# hv_pm.net
KiCad netlist of a schematic drawn in Altium Designer
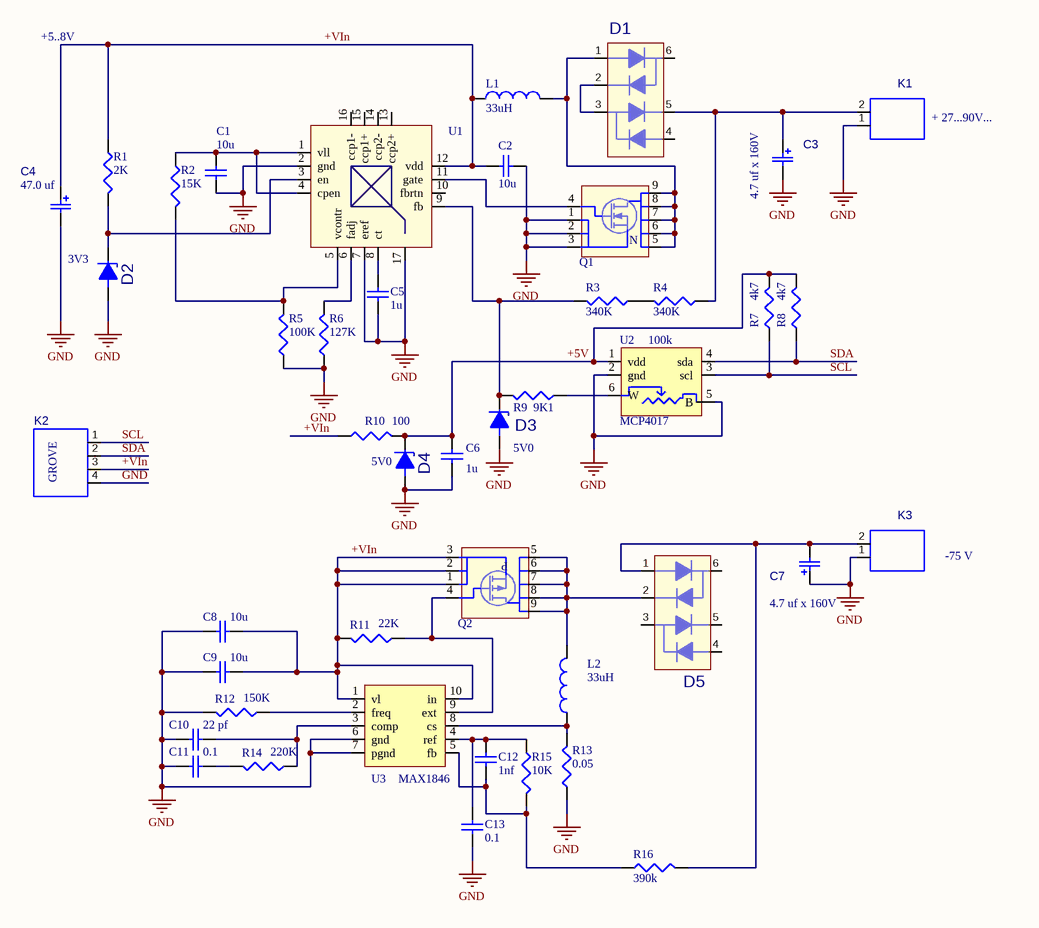
[diagram p0: hv_pm.SchDoc]

(export (version "E")
  (design (tool "Eeschema 10.0.6"))
  (components
    (comp (ref "C1")
      (value "10u")
      (footprint "SM0805")
      (description "Capacitor")
      (fields (field (name "Comment") "cap0805") (field (name "PUBLISHER") "Altium Limited"))
      (libsource (lib "alt2017") (part "cap0805"))
    )
    (comp (ref "C2")
      (value "10u")
      (footprint "SM0805")
      (description "Capacitor")
      (fields (field (name "Comment") "cap0805") (field (name "PUBLISHER") "Altium Limited"))
      (libsource (lib "alt2017") (part "cap0805"))
    )
    (comp (ref "C3")
      (value "CAP_d6.3x2.5mm")
      (footprint "CAP_d6.3x2.5mm")
      (fields (field (name "ALTIUM_UNNAMED_1") "4.7 uf x 160V"))
      (libsource (lib "alt2017") (part "CAP_d6.3x2.5mm"))
    )
    (comp (ref "C4")
      (value "CAP_POL_SMB")
      (footprint "alt_vovan:CAP_POL_SMB")
      (description "CAP_POL_SMB(3528)")
      (fields (field (name "ALTIUM_UNNAMED_1") "47.0 uf"))
      (libsource (lib "alt2017") (part "CAP_POL_SMB"))
    )
    (comp (ref "C5")
      (value "1u")
      (footprint "SM0805")
      (description "Capacitor")
      (fields (field (name "Comment") "cap0805") (field (name "PUBLISHER") "Altium Limited"))
      (libsource (lib "alt2017") (part "cap0805"))
    )
    (comp (ref "C6")
      (value "1u")
      (footprint "SM0805")
      (description "Capacitor")
      (fields (field (name "Comment") "cap0805") (field (name "PUBLISHER") "Altium Limited"))
      (libsource (lib "alt2017") (part "cap0805"))
    )
    (comp (ref "C7")
      (value "CAP_d6.3x2.5mm")
      (footprint "CAP_d6.3x2.5mm")
      (fields (field (name "ALTIUM_UNNAMED_1") "4.7 uf x 160V"))
      (libsource (lib "alt2017") (part "CAP_d6.3x2.5mm"))
    )
    (comp (ref "C8")
      (value "10u")
      (footprint "SM0805")
      (description "Capacitor")
      (fields (field (name "Comment") "cap0805") (field (name "PUBLISHER") "Altium Limited"))
      (libsource (lib "alt2017") (part "cap0805"))
    )
    (comp (ref "C9")
      (value "10u")
      (footprint "SM0805")
      (description "Capacitor")
      (fields (field (name "Comment") "cap0805") (field (name "PUBLISHER") "Altium Limited"))
      (libsource (lib "alt2017") (part "cap0805"))
    )
    (comp (ref "C10")
      (value "22 pf")
      (footprint "SM0805")
      (description "Capacitor")
      (fields (field (name "Comment") "cap0805") (field (name "PUBLISHER") "Altium Limited"))
      (libsource (lib "alt2017") (part "cap0805"))
    )
    (comp (ref "C11")
      (value "0.1")
      (footprint "SM0805")
      (description "Capacitor")
      (fields (field (name "Comment") "cap0805") (field (name "PUBLISHER") "Altium Limited"))
      (libsource (lib "alt2017") (part "cap0805"))
    )
    (comp (ref "C12")
      (value "1nf")
      (footprint "SM0805")
      (description "Capacitor")
      (fields (field (name "Comment") "cap0805") (field (name "PUBLISHER") "Altium Limited"))
      (libsource (lib "alt2017") (part "cap0805"))
    )
    (comp (ref "C13")
      (value "0.1")
      (footprint "SM0805")
      (description "Capacitor")
      (fields (field (name "Comment") "cap0805") (field (name "PUBLISHER") "Altium Limited"))
      (libsource (lib "alt2017") (part "cap0805"))
    )
    (comp (ref "D1")
      (value "BAV99S")
      (footprint "SOT-363")
      (description "sot343 diodes pack")
      (libsource (lib "alt2017") (part "BAV99S"))
    )
    (comp (ref "D2")
      (value "DiodeZener_SOD123")
      (footprint "SOD123")
      (description "SOD123")
      (libsource (lib "alt2017") (part "DiodeZener_SOD123"))
    )
    (comp (ref "D3")
      (value "DiodeZener_SOD123")
      (footprint "SOD123")
      (description "SOD123")
      (libsource (lib "alt2017") (part "DiodeZener_SOD123"))
    )
    (comp (ref "D4")
      (value "DiodeZener_SOD123")
      (footprint "SOD123")
      (description "SOD123")
      (libsource (lib "alt2017") (part "DiodeZener_SOD123"))
    )
    (comp (ref "D5")
      (value "BAV99S")
      (footprint "SOT-363")
      (description "sot343 diodes pack")
      (libsource (lib "alt2017") (part "BAV99S"))
    )
    (comp (ref "K1") (value "1x2PLS") (footprint "JUMPER2") (libsource (lib "alt2017") (part "1x2PLS")))
    (comp (ref "K2")
      (value "Grove_4pin, through hole")
      (footprint "Grove 4 pin")
      (description "4 pin vertical 2mm")
      (libsource (lib "alt2017") (part "Grove_4pin, through hole"))
    )
    (comp (ref "K3") (value "1x2PLS") (footprint "JUMPER2") (libsource (lib "alt2017") (part "1x2PLS")))
    (comp (ref "L1")
      (value "inductance SMT 3.2x4.5 mm")
      (footprint "inductor_LQH43PN")
      (fields (field (name "ALTIUM_UNNAMED_1") "33uH"))
      (libsource (lib "alt2017") (part "inductor_LQH43PN"))
    )
    (comp (ref "L2")
      (value "inductance SMT 3.2x4.5 mm")
      (footprint "inductor_LQH43PN")
      (fields (field (name "ALTIUM_UNNAMED_1") "33uH"))
      (libsource (lib "alt2017") (part "inductor_LQH43PN"))
    )
    (comp (ref "Q1")
      (value "MOSFET-N_BSZ42DN25NS3")
      (footprint "TSON 3.8x3.8mm -")
      (description "N-Channel MOSFET")
      (fields (field (name "PUBLISHER") "Altium Limited"))
      (libsource (lib "alt2017") (part "MOSFET-N_BSZ42DN25NS3"))
    )
    (comp (ref "Q2")
      (value "Si7113ADN")
      (footprint "TSON 3.8x3.8mm -")
      (description "P-Channel MOSFET")
      (fields (field (name "PUBLISHER") "Altium Limited"))
      (libsource (lib "alt2017") (part "MOSFET-P_Si7113ADN"))
    )
    (comp (ref "R1")
      (value "2K")
      (footprint "SM0805")
      (description "Resistor")
      (fields (field (name "Comment") "res0805") (field (name "PUBLISHER") "Altium Limited"))
      (libsource (lib "alt2017") (part "res0805"))
    )
    (comp (ref "R2")
      (value "15K")
      (footprint "SM0805")
      (description "Resistor")
      (fields (field (name "Comment") "res0805") (field (name "PUBLISHER") "Altium Limited"))
      (libsource (lib "alt2017") (part "res0805"))
    )
    (comp (ref "R3")
      (value "340K")
      (footprint "SM0805")
      (description "Resistor")
      (fields (field (name "Comment") "res0805") (field (name "PUBLISHER") "Altium Limited"))
      (libsource (lib "alt2017") (part "res0805"))
    )
    (comp (ref "R4")
      (value "340K")
      (footprint "SM0805")
      (description "Resistor")
      (fields (field (name "Comment") "res0805") (field (name "PUBLISHER") "Altium Limited"))
      (libsource (lib "alt2017") (part "res0805"))
    )
    (comp (ref "R5")
      (value "100K")
      (footprint "SM0805")
      (description "Resistor")
      (fields (field (name "Comment") "res0805") (field (name "PUBLISHER") "Altium Limited"))
      (libsource (lib "alt2017") (part "res0805"))
    )
    (comp (ref "R6")
      (value "127K")
      (footprint "SM0805")
      (description "Resistor")
      (fields (field (name "Comment") "res0805") (field (name "PUBLISHER") "Altium Limited"))
      (libsource (lib "alt2017") (part "res0805"))
    )
    (comp (ref "R7")
      (value "4k7")
      (footprint "SM0805")
      (description "Resistor")
      (fields (field (name "Comment") "res0805") (field (name "PUBLISHER") "Altium Limited"))
      (libsource (lib "alt2017") (part "res0805"))
    )
    (comp (ref "R8")
      (value "4k7")
      (footprint "SM0805")
      (description "Resistor")
      (fields (field (name "Comment") "res0805") (field (name "PUBLISHER") "Altium Limited"))
      (libsource (lib "alt2017") (part "res0805"))
    )
    (comp (ref "R9")
      (value "9K1")
      (footprint "SM0805")
      (description "Resistor")
      (fields (field (name "Comment") "res0805") (field (name "PUBLISHER") "Altium Limited"))
      (libsource (lib "alt2017") (part "res0805"))
    )
    (comp (ref "R10")
      (value "100")
      (footprint "SM0805")
      (description "Resistor")
      (fields (field (name "Comment") "res0805") (field (name "PUBLISHER") "Altium Limited"))
      (libsource (lib "alt2017") (part "res0805"))
    )
    (comp (ref "R11")
      (value "22K")
      (footprint "SM0805")
      (description "Resistor")
      (fields (field (name "Comment") "res0805") (field (name "PUBLISHER") "Altium Limited"))
      (libsource (lib "alt2017") (part "res0805"))
    )
    (comp (ref "R12")
      (value "150K")
      (footprint "SM0805")
      (description "Resistor")
      (fields (field (name "Comment") "res0805") (field (name "PUBLISHER") "Altium Limited"))
      (libsource (lib "alt2017") (part "res0805"))
    )
    (comp (ref "R13")
      (value "0.05")
      (footprint "smt2512")
      (description "Resistor")
      (fields (field (name "Comment") "res2512") (field (name "PUBLISHER") "Altium Limited"))
      (libsource (lib "alt2017") (part "res2512"))
    )
    (comp (ref "R14")
      (value "220K")
      (footprint "SM0805")
      (description "Resistor")
      (fields (field (name "Comment") "res0805") (field (name "PUBLISHER") "Altium Limited"))
      (libsource (lib "alt2017") (part "res0805"))
    )
    (comp (ref "R15")
      (value "10K")
      (footprint "SM0805")
      (description "Resistor")
      (fields (field (name "Comment") "res0805") (field (name "PUBLISHER") "Altium Limited"))
      (libsource (lib "alt2017") (part "res0805"))
    )
    (comp (ref "R16")
      (value "390k")
      (footprint "SM0805")
      (description "Resistor")
      (fields (field (name "Comment") "res0805") (field (name "PUBLISHER") "Altium Limited"))
      (libsource (lib "alt2017") (part "res0805"))
    )
    (comp (ref "U1")
      (value "boost converter")
      (footprint "QFN-16 3x3mm")
      (description "qfn16")
      (libsource (lib "alt2017") (part "HV9150"))
    )
    (comp (ref "U2")
      (value "MCP4017")
      (footprint "sc70-6")
      (description "I2C 128 tap digital pot")
      (libsource (lib "alt2017") (part "MCP4017"))
    )
    (comp (ref "U3")
      (value "MAX1846")
      (footprint "MSOP-10_M")
      (description "non-inverting buffer sot23-5")
      (libsource (lib "alt2017") (part "MAX1846"))
    )
  )
  (nets
    (net (code "1") (name "/+5V") (class "Default")
      (node (ref "C6") (pin "2") (pinfunction "2_2") (pintype "passive"))
      (node (ref "D4") (pin "2") (pinfunction "k_2") (pintype "passive"))
      (node (ref "R10") (pin "2") (pinfunction "2_2") (pintype "passive"))
      (node (ref "R7") (pin "2") (pinfunction "2_2") (pintype "passive"))
      (node (ref "R8") (pin "2") (pinfunction "2_2") (pintype "passive"))
      (node (ref "U2") (pin "1") (pinfunction "vdd_1") (pintype "passive"))
    )
    (net (code "2") (name "/+VIn") (class "Default")
      (node (ref "C2") (pin "2") (pinfunction "2_2") (pintype "passive"))
      (node (ref "C4") (pin "1") (pinfunction "a_1") (pintype "passive"))
      (node (ref "C8") (pin "2") (pinfunction "2_2") (pintype "passive"))
      (node (ref "C9") (pin "2") (pinfunction "2_2") (pintype "passive"))
      (node (ref "K2") (pin "3") (pinfunction "3_3") (pintype "passive"))
      (node (ref "L1") (pin "1") (pinfunction "1_1") (pintype "passive"))
      (node (ref "Q2") (pin "1") (pinfunction "s1_1") (pintype "passive"))
      (node (ref "Q2") (pin "2") (pinfunction "s2_2") (pintype "passive"))
      (node (ref "Q2") (pin "3") (pinfunction "s3_3") (pintype "passive"))
      (node (ref "R1") (pin "1") (pinfunction "1_1") (pintype "passive"))
      (node (ref "R10") (pin "1") (pinfunction "1_1") (pintype "passive"))
      (node (ref "R11") (pin "2") (pinfunction "2_2") (pintype "passive"))
      (node (ref "U1") (pin "12") (pinfunction "vdd_12") (pintype "passive"))
      (node (ref "U3") (pin "1") (pinfunction "vl_1") (pintype "passive"))
      (node (ref "U3") (pin "10") (pinfunction "in_10") (pintype "passive"))
    )
    (net (code "3") (name "/SCL") (class "Default")
      (node (ref "K2") (pin "1") (pinfunction "1_1") (pintype "passive"))
      (node (ref "R7") (pin "1") (pinfunction "1_1") (pintype "passive"))
      (node (ref "U2") (pin "3") (pinfunction "scl_3") (pintype "passive"))
    )
    (net (code "4") (name "/SDA") (class "Default")
      (node (ref "K2") (pin "2") (pinfunction "2_2") (pintype "passive"))
      (node (ref "R8") (pin "1") (pinfunction "1_1") (pintype "passive"))
      (node (ref "U2") (pin "4") (pinfunction "sda_4") (pintype "passive"))
    )
    (net (code "5") (name "GND") (class "Default")
      (node (ref "C1") (pin "1") (pinfunction "1_1") (pintype "passive"))
      (node (ref "C10") (pin "1") (pinfunction "1_1") (pintype "passive"))
      (node (ref "C11") (pin "1") (pinfunction "1_1") (pintype "passive"))
      (node (ref "C13") (pin "1") (pinfunction "1_1") (pintype "passive"))
      (node (ref "C2") (pin "1") (pinfunction "1_1") (pintype "passive"))
      (node (ref "C3") (pin "2") (pinfunction "b_2") (pintype "passive"))
      (node (ref "C4") (pin "2") (pinfunction "b_2") (pintype "passive"))
      (node (ref "C5") (pin "2") (pinfunction "2_2") (pintype "passive"))
      (node (ref "C6") (pin "1") (pinfunction "1_1") (pintype "passive"))
      (node (ref "C7") (pin "1") (pinfunction "a_1") (pintype "passive"))
      (node (ref "C8") (pin "1") (pinfunction "1_1") (pintype "passive"))
      (node (ref "C9") (pin "1") (pinfunction "1_1") (pintype "passive"))
      (node (ref "D2") (pin "1") (pinfunction "a_1") (pintype "passive"))
      (node (ref "D3") (pin "1") (pinfunction "a_1") (pintype "passive"))
      (node (ref "D4") (pin "1") (pinfunction "a_1") (pintype "passive"))
      (node (ref "K1") (pin "1") (pinfunction "1_1") (pintype "passive"))
      (node (ref "K2") (pin "4") (pinfunction "4_4") (pintype "passive"))
      (node (ref "K3") (pin "1") (pinfunction "1_1") (pintype "passive"))
      (node (ref "Q1") (pin "1") (pinfunction "s1_1") (pintype "passive"))
      (node (ref "Q1") (pin "2") (pinfunction "s2_2") (pintype "passive"))
      (node (ref "Q1") (pin "3") (pinfunction "s3_3") (pintype "passive"))
      (node (ref "R12") (pin "2") (pinfunction "2_2") (pintype "passive"))
      (node (ref "R13") (pin "1") (pinfunction "1_1") (pintype "passive"))
      (node (ref "R5") (pin "1") (pinfunction "1_1") (pintype "passive"))
      (node (ref "R6") (pin "1") (pinfunction "1_1") (pintype "passive"))
      (node (ref "U1") (pin "17") (pintype "passive"))
      (node (ref "U1") (pin "2") (pinfunction "gnd_2") (pintype "passive"))
      (node (ref "U1") (pin "7") (pinfunction "eref_7") (pintype "passive"))
      (node (ref "U2") (pin "2") (pinfunction "gnd_2") (pintype "passive"))
      (node (ref "U2") (pin "5") (pinfunction "B_5") (pintype "passive"))
      (node (ref "U3") (pin "6") (pinfunction "gnd_6") (pintype "passive"))
      (node (ref "U3") (pin "7") (pinfunction "pgnd_7") (pintype "passive"))
    )
    (net (code "6") (name "Net-(C3-a)") (class "Default")
      (node (ref "C3") (pin "1") (pinfunction "a_1") (pintype "passive"))
      (node (ref "D1") (pin "5") (pinfunction "k_5") (pintype "passive"))
      (node (ref "K1") (pin "2") (pinfunction "2_2") (pintype "passive"))
      (node (ref "R4") (pin "1") (pinfunction "1_1") (pintype "passive"))
    )
    (net (code "7") (name "Net-(C7-b)") (class "Default")
      (node (ref "C7") (pin "2") (pinfunction "b_2") (pintype "passive"))
      (node (ref "D5") (pin "1") (pinfunction "a_1") (pintype "passive"))
      (node (ref "K3") (pin "2") (pinfunction "2_2") (pintype "passive"))
      (node (ref "R16") (pin "2") (pinfunction "2_2") (pintype "passive"))
    )
    (net (code "8") (name "Net-(C11-Pad2)") (class "Default")
      (node (ref "C11") (pin "2") (pinfunction "2_2") (pintype "passive"))
      (node (ref "R14") (pin "2") (pinfunction "2_2") (pintype "passive"))
    )
    (net (code "9") (name "Net-(D1-a)") (class "Default")
      (node (ref "D1") (pin "1") (pinfunction "a_1") (pintype "passive"))
      (node (ref "L1") (pin "2") (pinfunction "2_2") (pintype "passive"))
      (node (ref "Q1") (pin "5") (pinfunction "d1_5") (pintype "passive"))
      (node (ref "Q1") (pin "6") (pinfunction "d2_6") (pintype "passive"))
      (node (ref "Q1") (pin "7") (pinfunction "d3_7") (pintype "passive"))
      (node (ref "Q1") (pin "8") (pinfunction "d4_8") (pintype "passive"))
      (node (ref "Q1") (pin "9") (pinfunction "d4_9") (pintype "passive"))
    )
    (net (code "10") (name "Net-(D1-k-Pad2)") (class "Default")
      (node (ref "D1") (pin "2") (pinfunction "k_2") (pintype "passive"))
      (node (ref "D1") (pin "3") (pinfunction "k_3") (pintype "passive"))
    )
    (net (code "11") (name "Net-(D2-k)") (class "Default")
      (node (ref "D2") (pin "2") (pinfunction "k_2") (pintype "passive"))
      (node (ref "R1") (pin "2") (pinfunction "2_2") (pintype "passive"))
      (node (ref "U1") (pin "3") (pinfunction "en_3") (pintype "passive"))
    )
    (net (code "12") (name "Net-(D3-k)") (class "Default")
      (node (ref "D3") (pin "2") (pinfunction "k_2") (pintype "passive"))
      (node (ref "R3") (pin "2") (pinfunction "2_2") (pintype "passive"))
      (node (ref "R9") (pin "2") (pinfunction "2_2") (pintype "passive"))
      (node (ref "U1") (pin "9") (pinfunction "fb_9") (pintype "passive"))
    )
    (net (code "13") (name "Net-(Q1-Gate)") (class "Default")
      (node (ref "Q1") (pin "4") (pinfunction "Gate_4") (pintype "passive"))
      (node (ref "U1") (pin "11") (pinfunction "gate_11") (pintype "passive"))
    )
    (net (code "14") (name "Net-(Q2-Gate)") (class "Default")
      (node (ref "Q2") (pin "4") (pinfunction "Gate_4") (pintype "passive"))
      (node (ref "R11") (pin "1") (pinfunction "1_1") (pintype "passive"))
      (node (ref "U3") (pin "9") (pinfunction "ext_9") (pintype "passive"))
    )
    (net (code "15") (name "Net-(Q2-d1)") (class "Default")
      (node (ref "D5") (pin "2") (pinfunction "k_2") (pintype "passive"))
      (node (ref "L2") (pin "2") (pinfunction "2_2") (pintype "passive"))
      (node (ref "Q2") (pin "5") (pinfunction "d1_5") (pintype "passive"))
      (node (ref "Q2") (pin "6") (pinfunction "d2_6") (pintype "passive"))
      (node (ref "Q2") (pin "7") (pinfunction "d3_7") (pintype "passive"))
      (node (ref "Q2") (pin "8") (pinfunction "d4_8") (pintype "passive"))
      (node (ref "Q2") (pin "9") (pinfunction "d4_9") (pintype "passive"))
    )
    (net (code "16") (name "Net-(R3-Pad1)") (class "Default")
      (node (ref "R3") (pin "1") (pinfunction "1_1") (pintype "passive"))
      (node (ref "R4") (pin "2") (pinfunction "2_2") (pintype "passive"))
    )
    (net (code "17") (name "Net-(U1-cpen)") (class "Default")
      (node (ref "C1") (pin "2") (pinfunction "2_2") (pintype "passive"))
      (node (ref "R2") (pin "1") (pinfunction "1_1") (pintype "passive"))
      (node (ref "U1") (pin "1") (pinfunction "vll_1") (pintype "passive"))
      (node (ref "U1") (pin "4") (pinfunction "cpen_4") (pintype "passive"))
    )
    (net (code "18") (name "Net-(U1-ct)") (class "Default")
      (node (ref "C5") (pin "1") (pinfunction "1_1") (pintype "passive"))
      (node (ref "U1") (pin "8") (pinfunction "ct_8") (pintype "passive"))
    )
    (net (code "19") (name "Net-(U1-fadj)") (class "Default")
      (node (ref "R6") (pin "2") (pinfunction "2_2") (pintype "passive"))
      (node (ref "U1") (pin "6") (pinfunction "fadj_6") (pintype "passive"))
    )
    (net (code "20") (name "Net-(U1-vcontr)") (class "Default")
      (node (ref "R2") (pin "2") (pinfunction "2_2") (pintype "passive"))
      (node (ref "R5") (pin "2") (pinfunction "2_2") (pintype "passive"))
      (node (ref "U1") (pin "5") (pinfunction "vcontr_5") (pintype "passive"))
    )
    (net (code "21") (name "Net-(U2-W)") (class "Default")
      (node (ref "R9") (pin "1") (pinfunction "1_1") (pintype "passive"))
      (node (ref "U2") (pin "6") (pinfunction "W_6") (pintype "passive"))
    )
    (net (code "22") (name "Net-(U3-comp)") (class "Default")
      (node (ref "C10") (pin "2") (pinfunction "2_2") (pintype "passive"))
      (node (ref "R14") (pin "1") (pinfunction "1_1") (pintype "passive"))
      (node (ref "U3") (pin "3") (pinfunction "comp_3") (pintype "passive"))
    )
    (net (code "23") (name "Net-(U3-cs)") (class "Default")
      (node (ref "L2") (pin "1") (pinfunction "1_1") (pintype "passive"))
      (node (ref "R13") (pin "2") (pinfunction "2_2") (pintype "passive"))
      (node (ref "U3") (pin "8") (pinfunction "cs_8") (pintype "passive"))
    )
    (net (code "24") (name "Net-(U3-fb)") (class "Default")
      (node (ref "C12") (pin "1") (pinfunction "1_1") (pintype "passive"))
      (node (ref "R15") (pin "2") (pinfunction "2_2") (pintype "passive"))
      (node (ref "R16") (pin "1") (pinfunction "1_1") (pintype "passive"))
      (node (ref "U3") (pin "5") (pinfunction "fb_5") (pintype "passive"))
    )
    (net (code "25") (name "Net-(U3-freq)") (class "Default")
      (node (ref "R12") (pin "1") (pinfunction "1_1") (pintype "passive"))
      (node (ref "U3") (pin "2") (pinfunction "freq_2") (pintype "passive"))
    )
    (net (code "26") (name "Net-(U3-ref)") (class "Default")
      (node (ref "C12") (pin "2") (pinfunction "2_2") (pintype "passive"))
      (node (ref "C13") (pin "2") (pinfunction "2_2") (pintype "passive"))
      (node (ref "R15") (pin "1") (pinfunction "1_1") (pintype "passive"))
      (node (ref "U3") (pin "4") (pinfunction "ref_4") (pintype "passive"))
    )
    (net (code "27") (name "unconnected-(D1-k-Pad4)") (class "Default")
      (node (ref "D1") (pin "4") (pinfunction "k_4") (pintype "passive"))
    )
    (net (code "28") (name "unconnected-(D1-k-Pad6)") (class "Default")
      (node (ref "D1") (pin "6") (pinfunction "k_6") (pintype "passive"))
    )
    (net (code "29") (name "unconnected-(D5-k-Pad3)") (class "Default")
      (node (ref "D5") (pin "3") (pinfunction "k_3") (pintype "passive"))
    )
    (net (code "30") (name "unconnected-(D5-k-Pad4)") (class "Default")
      (node (ref "D5") (pin "4") (pinfunction "k_4") (pintype "passive"))
    )
    (net (code "31") (name "unconnected-(D5-k-Pad5)") (class "Default")
      (node (ref "D5") (pin "5") (pinfunction "k_5") (pintype "passive"))
    )
    (net (code "32") (name "unconnected-(D5-k-Pad6)") (class "Default")
      (node (ref "D5") (pin "6") (pinfunction "k_6") (pintype "passive"))
    )
    (net (code "33") (name "unconnected-(U1-ccp1+-Pad15)") (class "Default")
      (node (ref "U1") (pin "15") (pinfunction "ccp1+_15") (pintype "passive"))
    )
    (net (code "34") (name "unconnected-(U1-ccp1--Pad16)") (class "Default")
      (node (ref "U1") (pin "16") (pinfunction "ccp1-_16") (pintype "passive"))
    )
    (net (code "35") (name "unconnected-(U1-ccp2+-Pad13)") (class "Default")
      (node (ref "U1") (pin "13") (pinfunction "ccp2+_13") (pintype "passive"))
    )
    (net (code "36") (name "unconnected-(U1-ccp2--Pad14)") (class "Default")
      (node (ref "U1") (pin "14") (pinfunction "ccp2-_14") (pintype "passive"))
    )
    (net (code "37") (name "unconnected-(U1-fbrtn-Pad10)") (class "Default")
      (node (ref "U1") (pin "10") (pinfunction "fbrtn_10") (pintype "passive"))
    )
  )
)
